# schematic.net
KiCad netlist of a schematic drawn in Altium Designer
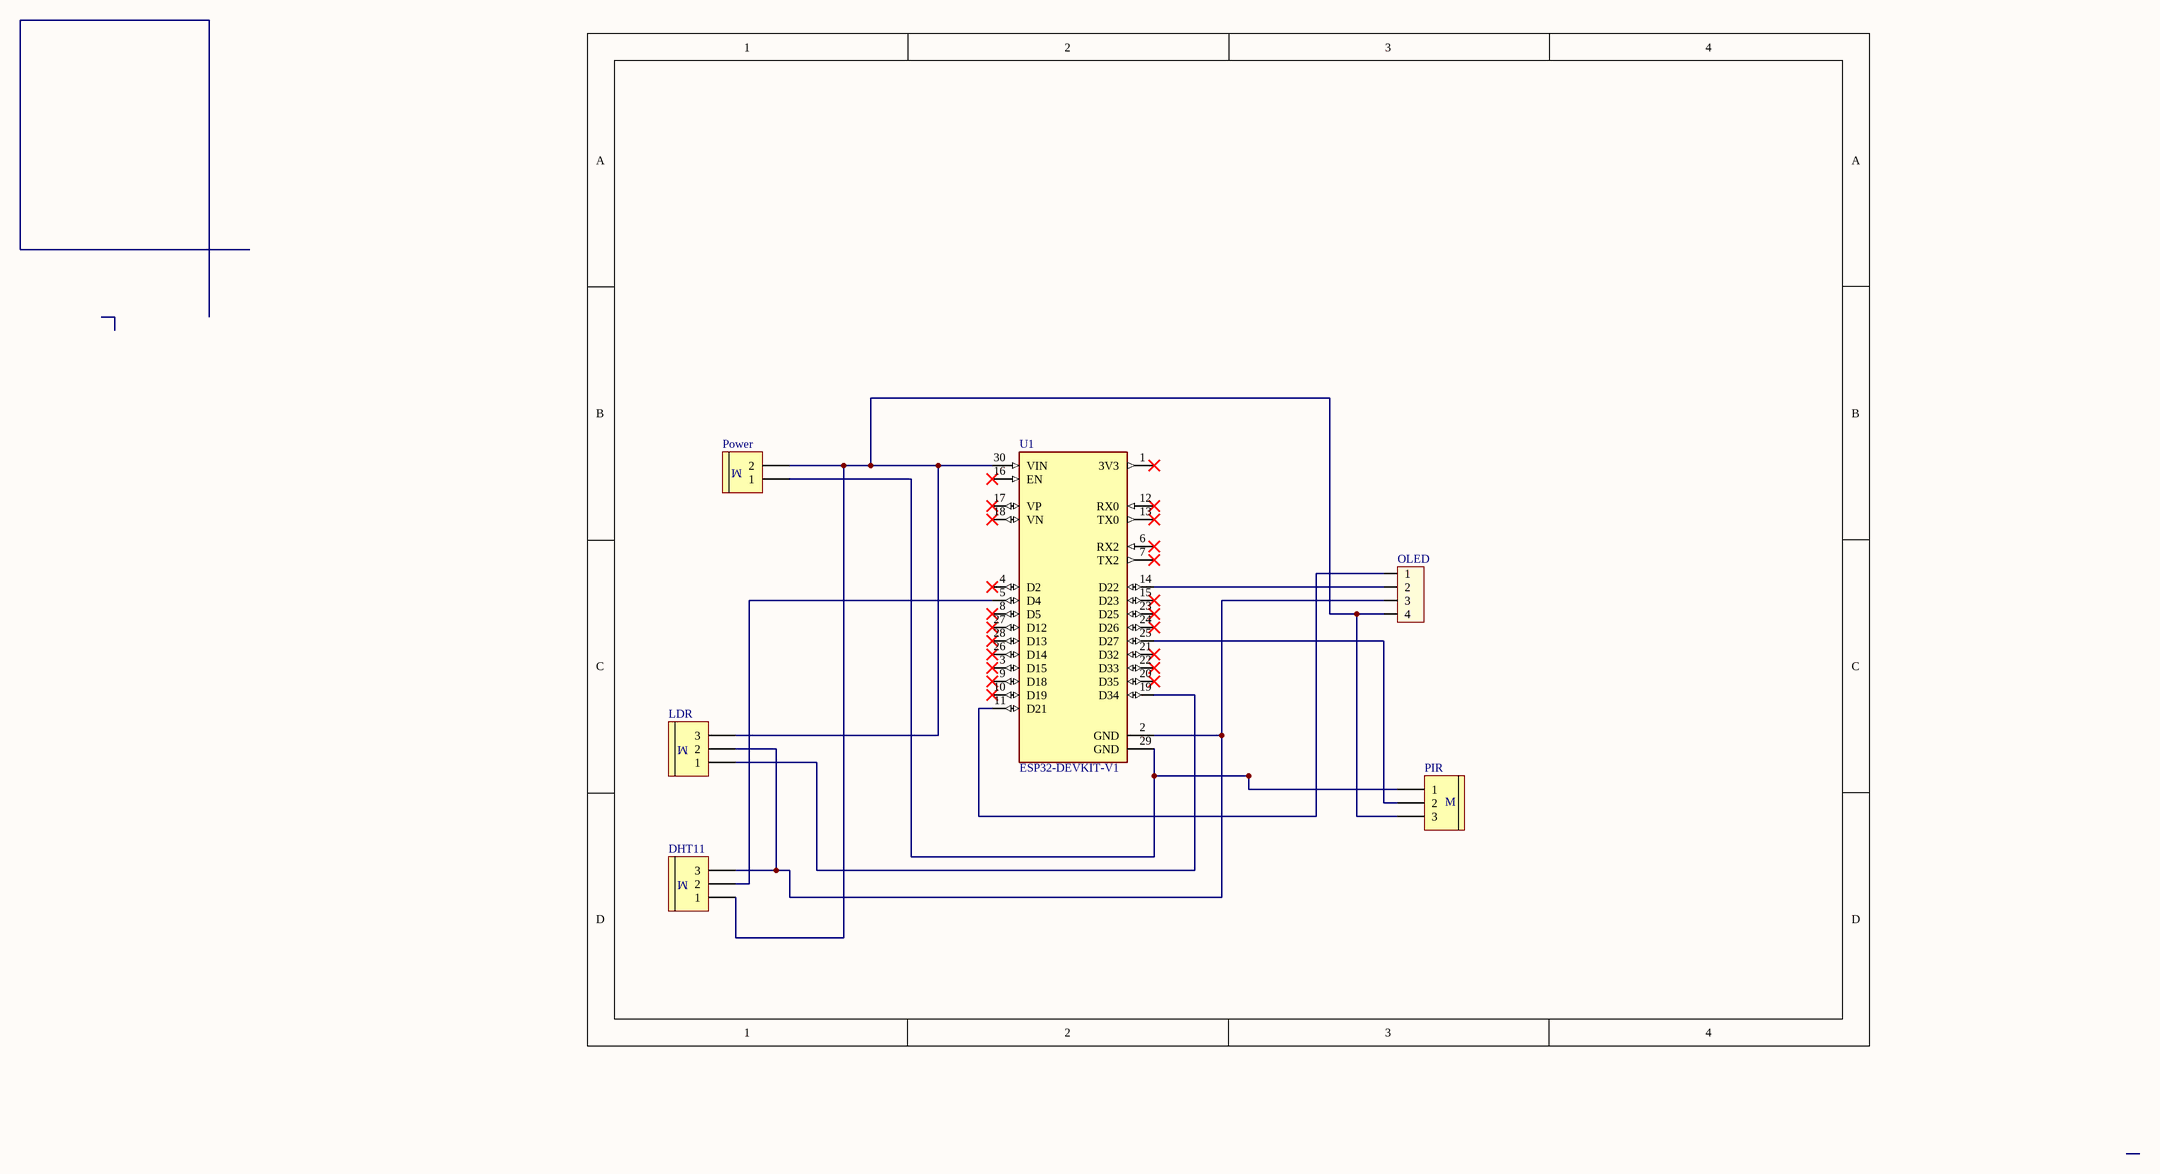
[diagram p0: schematic.SchDoc]

(export (version "E")
  (design (tool "Eeschema 10.0.6"))
  (components
    (comp (ref "DHT11")
      (value "Header 3 - M")
      (footprint "Medium - Header 3")
      (description "Header, 3-Pin, Medium")
      (fields (field (name "PUBLISHER") "Altium Limited"))
      (libsource (lib "") (part "Header 3 - M_1"))
    )
    (comp (ref "LDR")
      (value "Header 3 - M")
      (footprint "Medium - Header 3")
      (description "Header, 3-Pin, Medium")
      (fields (field (name "PUBLISHER") "Altium Limited"))
      (libsource (lib "") (part "Header 3 - M_1"))
    )
    (comp (ref "OLED")
      (value "Header 4")
      (footprint "HED4")
      (description "Header 4 (Green)")
      (libsource (lib "Cty1") (part "Hed4"))
    )
    (comp (ref "PIR")
      (value "Header 3 - M")
      (footprint "Medium - Header 3")
      (description "Header, 3-Pin, Medium")
      (fields (field (name "PUBLISHER") "Altium Limited"))
      (libsource (lib "Cty1") (part "Header 3 - M"))
    )
    (comp (ref "Power")
      (value "Header 2 - M")
      (footprint "Medium - Header 2")
      (description "Header, 2-Pin, Medium")
      (fields (field (name "PUBLISHER") "Altium Limited"))
      (libsource (lib "Cty1") (part "Header 2 - M"))
    )
    (comp (ref "U1")
      (value "ESP32-DEVKIT-V1")
      (footprint "MODULE_ESP32_DEVKIT_V1")
      (fields (field (name "MF") "Do it"))
      (libsource (lib "ESP32-DEVKIT-V1") (part "ESP32-DEVKIT-V1"))
    )
  )
  (nets
    (net (code "1") (name "Net-(DHT11-Pad3)") (class "Default")
      (node (ref "DHT11") (pin "3") (pinfunction "3_3") (pintype "passive"))
      (node (ref "LDR") (pin "2") (pinfunction "2_2") (pintype "passive"))
      (node (ref "OLED") (pin "3") (pinfunction "3_3") (pintype "passive"))
      (node (ref "U1") (pin "2") (pinfunction "GND_2") (pintype "power_in"))
    )
    (net (code "2") (name "Net-(PIR-Pad1)") (class "Default")
      (node (ref "PIR") (pin "1") (pinfunction "1_1") (pintype "passive"))
      (node (ref "Power") (pin "1") (pinfunction "1_1") (pintype "passive"))
      (node (ref "U1") (pin "29") (pinfunction "GND_29") (pintype "power_in"))
    )
    (net (code "3") (name "Net-(U1-D4)") (class "Default")
      (node (ref "DHT11") (pin "2") (pinfunction "2_2") (pintype "passive"))
      (node (ref "U1") (pin "5") (pinfunction "D4_5") (pintype "bidirectional"))
    )
    (net (code "4") (name "Net-(U1-D21)") (class "Default")
      (node (ref "OLED") (pin "1") (pinfunction "1_1") (pintype "passive"))
      (node (ref "U1") (pin "11") (pinfunction "D21_11") (pintype "bidirectional"))
    )
    (net (code "5") (name "Net-(U1-D22)") (class "Default")
      (node (ref "OLED") (pin "2") (pinfunction "2_2") (pintype "passive"))
      (node (ref "U1") (pin "14") (pinfunction "D22_14") (pintype "bidirectional"))
    )
    (net (code "6") (name "Net-(U1-D27)") (class "Default")
      (node (ref "PIR") (pin "2") (pinfunction "2_2") (pintype "passive"))
      (node (ref "U1") (pin "25") (pinfunction "D27_25") (pintype "bidirectional"))
    )
    (net (code "7") (name "Net-(U1-D34)") (class "Default")
      (node (ref "LDR") (pin "1") (pinfunction "1_1") (pintype "passive"))
      (node (ref "U1") (pin "19") (pinfunction "D34_19") (pintype "bidirectional"))
    )
    (net (code "8") (name "Net-(U1-VIN)") (class "Default")
      (node (ref "DHT11") (pin "1") (pinfunction "1_1") (pintype "passive"))
      (node (ref "LDR") (pin "3") (pinfunction "3_3") (pintype "passive"))
      (node (ref "OLED") (pin "4") (pinfunction "4_4") (pintype "passive"))
      (node (ref "PIR") (pin "3") (pinfunction "3_3") (pintype "passive"))
      (node (ref "Power") (pin "2") (pinfunction "2_2") (pintype "passive"))
      (node (ref "U1") (pin "30") (pinfunction "VIN_30") (pintype "input"))
    )
    (net (code "9") (name "unconnected-(U1-3V3-Pad1)") (class "Default")
      (node (ref "U1") (pin "1") (pinfunction "3V3_1") (pintype "output+no_connect"))
    )
    (net (code "10") (name "unconnected-(U1-D2-Pad4)") (class "Default")
      (node (ref "U1") (pin "4") (pinfunction "D2_4") (pintype "bidirectional+no_connect"))
    )
    (net (code "11") (name "unconnected-(U1-D5-Pad8)") (class "Default")
      (node (ref "U1") (pin "8") (pinfunction "D5_8") (pintype "bidirectional+no_connect"))
    )
    (net (code "12") (name "unconnected-(U1-D12-Pad27)") (class "Default")
      (node (ref "U1") (pin "27") (pinfunction "D12_27") (pintype "bidirectional+no_connect"))
    )
    (net (code "13") (name "unconnected-(U1-D13-Pad28)") (class "Default")
      (node (ref "U1") (pin "28") (pinfunction "D13_28") (pintype "bidirectional+no_connect"))
    )
    (net (code "14") (name "unconnected-(U1-D14-Pad26)") (class "Default")
      (node (ref "U1") (pin "26") (pinfunction "D14_26") (pintype "bidirectional+no_connect"))
    )
    (net (code "15") (name "unconnected-(U1-D15-Pad3)") (class "Default")
      (node (ref "U1") (pin "3") (pinfunction "D15_3") (pintype "bidirectional+no_connect"))
    )
    (net (code "16") (name "unconnected-(U1-D18-Pad9)") (class "Default")
      (node (ref "U1") (pin "9") (pinfunction "D18_9") (pintype "bidirectional+no_connect"))
    )
    (net (code "17") (name "unconnected-(U1-D19-Pad10)") (class "Default")
      (node (ref "U1") (pin "10") (pinfunction "D19_10") (pintype "bidirectional+no_connect"))
    )
    (net (code "18") (name "unconnected-(U1-D23-Pad15)") (class "Default")
      (node (ref "U1") (pin "15") (pinfunction "D23_15") (pintype "bidirectional+no_connect"))
    )
    (net (code "19") (name "unconnected-(U1-D25-Pad23)") (class "Default")
      (node (ref "U1") (pin "23") (pinfunction "D25_23") (pintype "bidirectional+no_connect"))
    )
    (net (code "20") (name "unconnected-(U1-D26-Pad24)") (class "Default")
      (node (ref "U1") (pin "24") (pinfunction "D26_24") (pintype "bidirectional+no_connect"))
    )
    (net (code "21") (name "unconnected-(U1-D32-Pad21)") (class "Default")
      (node (ref "U1") (pin "21") (pinfunction "D32_21") (pintype "bidirectional+no_connect"))
    )
    (net (code "22") (name "unconnected-(U1-D33-Pad22)") (class "Default")
      (node (ref "U1") (pin "22") (pinfunction "D33_22") (pintype "bidirectional+no_connect"))
    )
    (net (code "23") (name "unconnected-(U1-D35-Pad20)") (class "Default")
      (node (ref "U1") (pin "20") (pinfunction "D35_20") (pintype "bidirectional+no_connect"))
    )
    (net (code "24") (name "unconnected-(U1-EN-Pad16)") (class "Default")
      (node (ref "U1") (pin "16") (pinfunction "EN_16") (pintype "input+no_connect"))
    )
    (net (code "25") (name "unconnected-(U1-RX0-Pad12)") (class "Default")
      (node (ref "U1") (pin "12") (pinfunction "RX0_12") (pintype "input+no_connect"))
    )
    (net (code "26") (name "unconnected-(U1-RX2-Pad6)") (class "Default")
      (node (ref "U1") (pin "6") (pinfunction "RX2_6") (pintype "input+no_connect"))
    )
    (net (code "27") (name "unconnected-(U1-TX0-Pad13)") (class "Default")
      (node (ref "U1") (pin "13") (pinfunction "TX0_13") (pintype "output+no_connect"))
    )
    (net (code "28") (name "unconnected-(U1-TX2-Pad7)") (class "Default")
      (node (ref "U1") (pin "7") (pinfunction "TX2_7") (pintype "output+no_connect"))
    )
    (net (code "29") (name "unconnected-(U1-VN-Pad18)") (class "Default")
      (node (ref "U1") (pin "18") (pinfunction "VN_18") (pintype "bidirectional+no_connect"))
    )
    (net (code "30") (name "unconnected-(U1-VP-Pad17)") (class "Default")
      (node (ref "U1") (pin "17") (pinfunction "VP_17") (pintype "bidirectional+no_connect"))
    )
  )
)
